# ESP32.net
KiCad netlist of a schematic drawn in Altium Designer
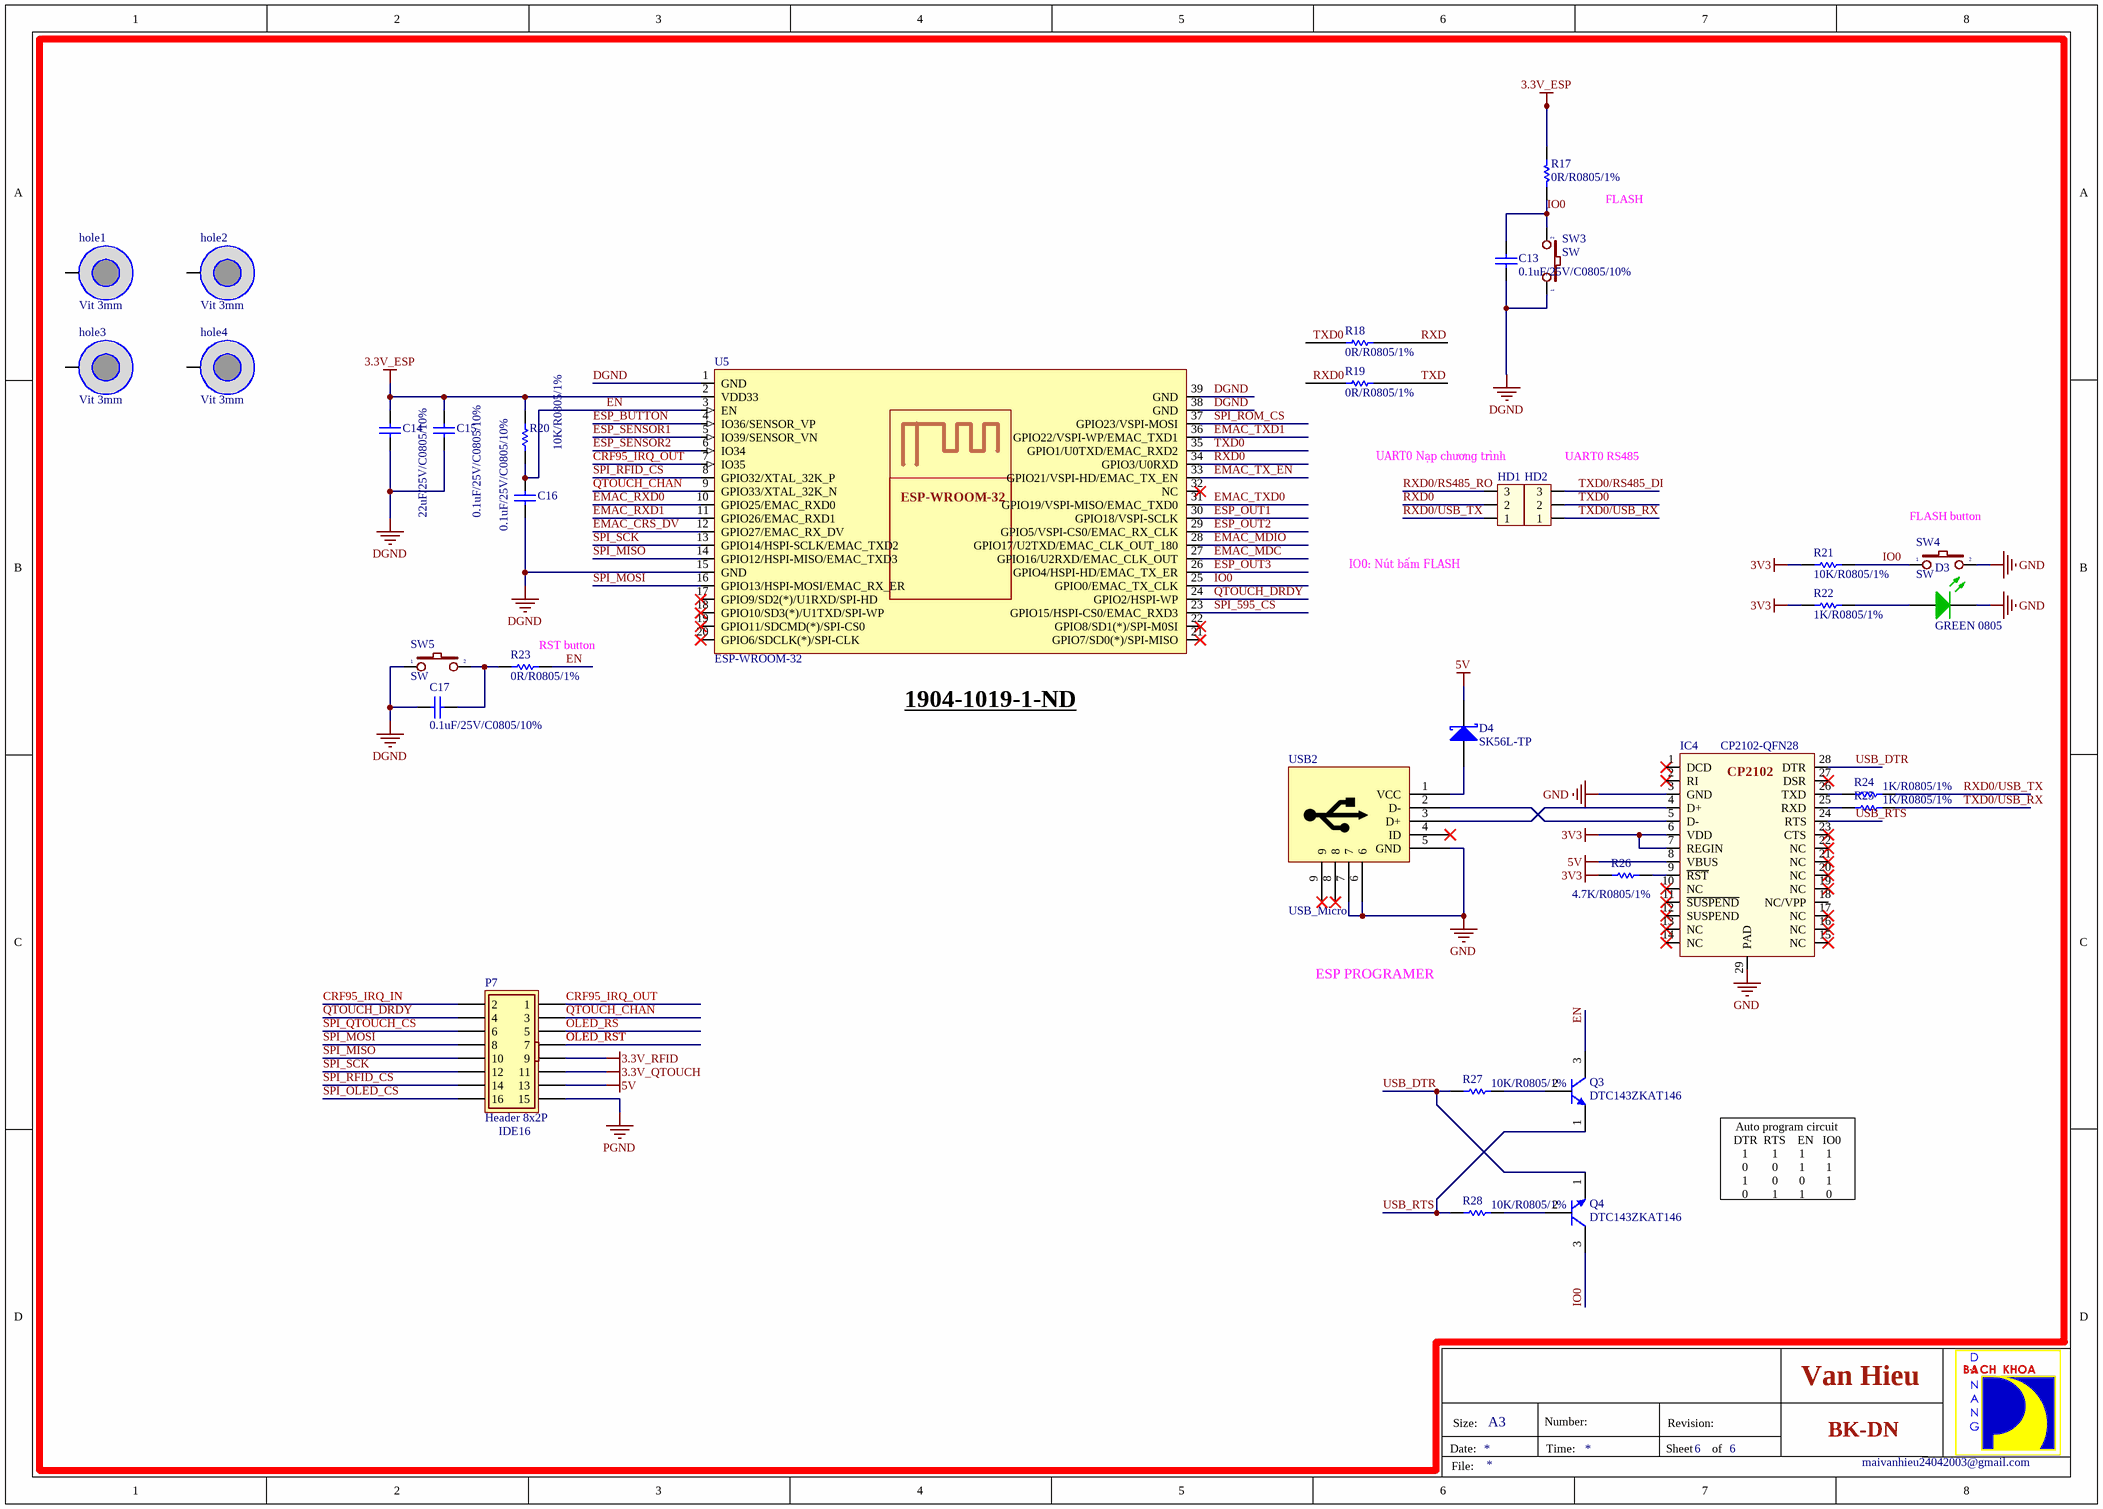
[diagram p0: ESP32.SchDoc]

(export (version "E")
  (design (tool "Eeschema 10.0.6"))
  (components
    (comp (ref "C13")
      (value "0.1uF/25V/C0805/10%")
      (footprint "CAP_CERA_C2012(CC0805INCH)")
      (description "0.1µF ±10% 25V Ceramic Capacitor X7R 0805 (2012 Metric)")
      (libsource (lib "GSHT_181013") (part "0.1uF/50V/C0603/10%"))
    )
    (comp (ref "C14")
      (value "22uF/25V/C0805/10%")
      (footprint "CAP_CERA_C2012(CC0805INCH)")
      (description "22µF ±20% 25V Ceramic Capacitor X5R 0805 (2012 Metric)")
      (fields (field (name "MANUFACTURER") "Tariff Applied"))
      (libsource (lib "GSHT_181013") (part "0.1uF/50V/C0603/10%"))
    )
    (comp (ref "C15")
      (value "0.1uF/25V/C0805/10%")
      (footprint "CAP_CERA_C2012(CC0805INCH)")
      (description "0.1µF ±10% 25V Ceramic Capacitor X7R 0805 (2012 Metric)")
      (libsource (lib "GSHT_181013") (part "0.1uF/50V/C0603/10%"))
    )
    (comp (ref "C16")
      (value "0.1uF/25V/C0805/10%")
      (footprint "CAP_CERA_C2012(CC0805INCH)")
      (description "0.1µF ±10% 25V Ceramic Capacitor X7R 0805 (2012 Metric)")
      (libsource (lib "GSHT_181013") (part "0.1uF/50V/C0603/10%"))
    )
    (comp (ref "C17")
      (value "0.1uF/25V/C0805/10%")
      (footprint "CAP_CERA_C2012(CC0805INCH)")
      (description "0.1µF ±10% 25V Ceramic Capacitor X7R 0805 (2012 Metric)")
      (libsource (lib "GSHT_181013") (part "0.1uF/50V/C0603/10%"))
    )
    (comp (ref "D3")
      (value "GREEN 0805")
      (footprint "Led 0805G")
      (description "Green 571nm LED Indication - Discrete 2V 0805 (2012 Metric)")
      (libsource (lib "GSHT_181013") (part "LED GREEN 0603"))
    )
    (comp (ref "D4")
      (value "SK56L-TP")
      (footprint "30# SK56L-TPMSCT-ND")
      (description "DIODE SCHOTTKY 60V 5A DO214AB")
      (libsource (lib "GSHT_181013") (part "30# SK56L-TP"))
    )
    (comp (ref "HD1") (value "Header 3") (footprint "Header_3") (libsource (lib "") (part "Header3_1")))
    (comp (ref "HD2") (value "Header 3") (footprint "Header_3") (libsource (lib "lpson") (part "Header3")))
    (comp (ref "hole1") (value "Vit 3mm") (footprint "Screw 3.0") (libsource (lib "lpson") (part "Vit 3mm")))
    (comp (ref "hole2") (value "Vit 3mm") (footprint "Screw 3.0") (libsource (lib "lpson") (part "Vit 3mm")))
    (comp (ref "hole3") (value "Vit 3mm") (footprint "Screw 3.0") (libsource (lib "lpson") (part "Vit 3mm")))
    (comp (ref "hole4") (value "Vit 3mm") (footprint "Screw 3.0") (libsource (lib "lpson") (part "Vit 3mm")))
    (comp (ref "IC4") (value "CP2102-QFN28") (footprint "CP2102") (libsource (lib "lpson") (part "CP2102")))
    (comp (ref "P7")
      (value "Header 8x2P")
      (footprint "LPSON_CON:Header IDE16 8x2 -")
      (description "IDE16 Đực Thẳng 2.54MM")
      (libsource (lib "lpson") (part "Header IDE 8x2P"))
    )
    (comp (ref "Q3")
      (value "DTC143ZKAT146")
      (footprint "6# DTC143ZKAT146-E")
      (description "Pre-Biased Bipolar Transistor (BJT) NPN - Pre-Biased 50V 100mA 250MHz 200mW Surface Mount SMT3")
      (libsource (lib "GSHT_181013") (part "6#DTC143ZKAT146"))
    )
    (comp (ref "Q4")
      (value "DTC143ZKAT146")
      (footprint "6# DTC143ZKAT146-E")
      (description "Pre-Biased Bipolar Transistor (BJT) NPN - Pre-Biased 50V 100mA 250MHz 200mW Surface Mount SMT3")
      (libsource (lib "GSHT_181013") (part "6#DTC143ZKAT146"))
    )
    (comp (ref "R17")
      (value "0R/R0805/1%")
      (footprint "Res 0805 SMD")
      (description "0 Ohms Jumper 0.125W, 1/8W Chip Resistor 0805 (2012 Metric) Automotive AEC-Q200 Thick Film")
      (libsource (lib "GSHT_181013") (part "200K/R0603/1%"))
    )
    (comp (ref "R18")
      (value "0R/R0805/1%")
      (footprint "Res 0805 SMD")
      (description "0 Ohms Jumper 0.125W, 1/8W Chip Resistor 0805 (2012 Metric) Automotive AEC-Q200 Thick Film")
      (libsource (lib "GSHT_181013") (part "10K/R0603/1%"))
    )
    (comp (ref "R19")
      (value "0R/R0805/1%")
      (footprint "Res 0805 SMD")
      (description "0 Ohms Jumper 0.125W, 1/8W Chip Resistor 0805 (2012 Metric) Automotive AEC-Q200 Thick Film")
      (libsource (lib "GSHT_181013") (part "10K/R0603/1%"))
    )
    (comp (ref "R20")
      (value "10K/R0805/1%")
      (footprint "Res 0805 SMD")
      (description "10 kOhms ±1% 0.125W, 1/8W Chip Resistor 0805 (2012 Metric) Thick Film")
      (libsource (lib "GSHT_181013") (part "200K/R0603/1%"))
    )
    (comp (ref "R21")
      (value "10K/R0805/1%")
      (footprint "Res 0805 SMD")
      (description "10 kOhms ±1% 0.125W, 1/8W Chip Resistor 0805 (2012 Metric) Thick Film")
      (libsource (lib "GSHT_181013") (part "200K/R0603/1%"))
    )
    (comp (ref "R22")
      (value "1K/R0805/1%")
      (footprint "Res 0805 SMD")
      (description "1 kOhms ±1% 0.125W, 1/8W Chip Resistor 0805 (2012 Metric) Automotive AEC-Q200 Thick Film")
      (libsource (lib "GSHT_181013") (part "200K/R0603/1%"))
    )
    (comp (ref "R23")
      (value "0R/R0805/1%")
      (footprint "Res 0805 SMD")
      (description "0 Ohms Jumper 0.125W, 1/8W Chip Resistor 0805 (2012 Metric) Automotive AEC-Q200 Thick Film")
      (libsource (lib "GSHT_181013") (part "200K/R0603/1%"))
    )
    (comp (ref "R24")
      (value "1K/R0805/1%")
      (footprint "Res 0805 SMD")
      (description "1 kOhms ±1% 0.125W, 1/8W Chip Resistor 0805 (2012 Metric) Automotive AEC-Q200 Thick Film")
      (libsource (lib "GSHT_181013") (part "34.8K/R0805/1%"))
    )
    (comp (ref "R25")
      (value "1K/R0805/1%")
      (footprint "Res 0805 SMD")
      (description "1 kOhms ±1% 0.125W, 1/8W Chip Resistor 0805 (2012 Metric) Automotive AEC-Q200 Thick Film")
      (libsource (lib "GSHT_181013") (part "34.8K/R0805/1%"))
    )
    (comp (ref "R26")
      (value "4.7K/R0805/1%")
      (footprint "Res 0805 SMD")
      (description "4.7 kOhms ±1% 0.125W, 1/8W Chip Resistor 0805 (2012 Metric) Thick Film")
      (libsource (lib "GSHT_181013") (part "34.8K/R0805/1%"))
    )
    (comp (ref "R27")
      (value "10K/R0805/1%")
      (footprint "Res 0805 SMD")
      (description "10 kOhms ±1% 0.125W, 1/8W Chip Resistor 0805 (2012 Metric) Thick Film")
      (libsource (lib "GSHT_181013") (part "34.8K/R0805/1%"))
    )
    (comp (ref "R28")
      (value "10K/R0805/1%")
      (footprint "Res 0805 SMD")
      (description "10 kOhms ±1% 0.125W, 1/8W Chip Resistor 0805 (2012 Metric) Thick Film")
      (libsource (lib "GSHT_181013") (part "34.8K/R0805/1%"))
    )
    (comp (ref "SW3")
      (value "SW")
      (footprint "BUTTON 2PIN TRON")
      (description "Switch button 2 pin")
      (libsource (lib "lpson") (part "SW2"))
    )
    (comp (ref "SW4")
      (value "SW")
      (footprint "BUTTON 2PIN TRON")
      (description "Switch button 2 pin")
      (libsource (lib "lpson") (part "SW2"))
    )
    (comp (ref "SW5")
      (value "SW")
      (footprint "BUTTON 2PIN TRON")
      (description "Switch button 2 pin")
      (libsource (lib "lpson") (part "SW2"))
    )
    (comp (ref "U5")
      (value "ESP-WROOM-32")
      (footprint "ESP32 WROOM")
      (libsource (lib "lpson") (part "ESP-WROOM-32"))
    )
    (comp (ref "USB2") (value "USB_Micro") (footprint "USBMNIB") (libsource (lib "lpson") (part "USB_MINI")))
  )
  (nets
    (net (code "1") (name "/CRF95_IRQ_IN") (class "Default")
      (node (ref "P7") (pin "2") (pinfunction "2_2") (pintype "passive"))
    )
    (net (code "2") (name "/CRF95_IRQ_OUT") (class "Default")
      (node (ref "P7") (pin "1") (pinfunction "1_1") (pintype "passive"))
      (node (ref "U5") (pin "7") (pinfunction "IO35_7") (pintype "input"))
    )
    (net (code "3") (name "/EMAC_CRS_DV") (class "Default")
      (node (ref "U5") (pin "12") (pinfunction "GPIO27/EMAC_RX_DV_12") (pintype "passive"))
    )
    (net (code "4") (name "/EMAC_MDC") (class "Default")
      (node (ref "U5") (pin "27") (pinfunction "GPIO16/U2RXD/EMAC_CLK_OUT_27") (pintype "passive"))
    )
    (net (code "5") (name "/EMAC_MDIO") (class "Default")
      (node (ref "U5") (pin "28") (pinfunction "GPIO17/U2TXD/EMAC_CLK_OUT_180_28") (pintype "passive"))
    )
    (net (code "6") (name "/EMAC_RXD0") (class "Default")
      (node (ref "U5") (pin "10") (pinfunction "GPIO25/EMAC_RXD0_10") (pintype "passive"))
    )
    (net (code "7") (name "/EMAC_RXD1") (class "Default")
      (node (ref "U5") (pin "11") (pinfunction "GPIO26/EMAC_RXD1_11") (pintype "passive"))
    )
    (net (code "8") (name "/EMAC_TXD0") (class "Default")
      (node (ref "U5") (pin "31") (pinfunction "GPIO19/VSPI-MISO/EMAC_TXD0_31") (pintype "passive"))
    )
    (net (code "9") (name "/EMAC_TXD1") (class "Default")
      (node (ref "U5") (pin "36") (pinfunction "GPIO22/VSPI-WP/EMAC_TXD1_36") (pintype "passive"))
    )
    (net (code "10") (name "/EMAC_TX_EN") (class "Default")
      (node (ref "U5") (pin "33") (pinfunction "GPIO21/VSPI-HD/EMAC_TX_EN_33") (pintype "passive"))
    )
    (net (code "11") (name "/EN") (class "Default")
      (node (ref "C16") (pin "2") (pinfunction "2_2") (pintype "passive"))
      (node (ref "Q3") (pin "3") (pinfunction "C_3") (pintype "passive"))
      (node (ref "R20") (pin "2") (pinfunction "2_2") (pintype "passive"))
      (node (ref "R23") (pin "2") (pinfunction "2_2") (pintype "passive"))
      (node (ref "U5") (pin "3") (pinfunction "EN_3") (pintype "input"))
    )
    (net (code "12") (name "/ESP_BUTTON") (class "Default")
      (node (ref "U5") (pin "4") (pinfunction "IO36/SENSOR_VP_4") (pintype "input"))
    )
    (net (code "13") (name "/ESP_OUT1") (class "Default")
      (node (ref "U5") (pin "30") (pinfunction "GPIO18/VSPI-SCLK_30") (pintype "passive"))
    )
    (net (code "14") (name "/ESP_OUT2") (class "Default")
      (node (ref "U5") (pin "29") (pinfunction "GPIO5/VSPI-CS0/EMAC_RX_CLK_29") (pintype "passive"))
    )
    (net (code "15") (name "/ESP_OUT3") (class "Default")
      (node (ref "U5") (pin "26") (pinfunction "GPIO4/HSPI-HD/EMAC_TX_ER_26") (pintype "passive"))
    )
    (net (code "16") (name "/ESP_SENSOR1") (class "Default")
      (node (ref "U5") (pin "5") (pinfunction "IO39/SENSOR_VN_5") (pintype "input"))
    )
    (net (code "17") (name "/ESP_SENSOR2") (class "Default")
      (node (ref "U5") (pin "6") (pinfunction "IO34_6") (pintype "input"))
    )
    (net (code "18") (name "/IO0") (class "Default")
      (node (ref "C13") (pin "1") (pinfunction "1_1") (pintype "passive"))
      (node (ref "Q4") (pin "3") (pinfunction "C_3") (pintype "passive"))
      (node (ref "R17") (pin "1") (pinfunction "1_1") (pintype "passive"))
      (node (ref "R21") (pin "2") (pinfunction "2_2") (pintype "passive"))
      (node (ref "SW3") (pin "2") (pinfunction "2_2") (pintype "passive"))
      (node (ref "SW4") (pin "1") (pinfunction "1_1") (pintype "passive"))
      (node (ref "U5") (pin "25") (pinfunction "GPIO0/EMAC_TX_CLK_25") (pintype "passive"))
    )
    (net (code "19") (name "/OLED_RS") (class "Default")
      (node (ref "P7") (pin "5") (pinfunction "5_5") (pintype "passive"))
    )
    (net (code "20") (name "/OLED_RST") (class "Default")
      (node (ref "P7") (pin "7") (pinfunction "7_7") (pintype "passive"))
    )
    (net (code "21") (name "/QTOUCH_CHAN") (class "Default")
      (node (ref "P7") (pin "3") (pinfunction "3_3") (pintype "passive"))
      (node (ref "U5") (pin "9") (pinfunction "GPIO33/XTAL_32K_N_9") (pintype "passive"))
    )
    (net (code "22") (name "/QTOUCH_DRDY") (class "Default")
      (node (ref "P7") (pin "4") (pinfunction "4_4") (pintype "passive"))
      (node (ref "U5") (pin "24") (pinfunction "GPIO2/HSPI-WP_24") (pintype "passive"))
    )
    (net (code "23") (name "/RXD") (class "Default")
      (node (ref "R18") (pin "1") (pinfunction "1_1") (pintype "passive"))
    )
    (net (code "24") (name "/RXD0") (class "Default")
      (node (ref "HD1") (pin "2") (pinfunction "2_2") (pintype "passive"))
      (node (ref "R19") (pin "2") (pinfunction "2_2") (pintype "passive"))
      (node (ref "U5") (pin "34") (pinfunction "GPIO3/U0RXD_34") (pintype "passive"))
    )
    (net (code "25") (name "/RXD0{slash}RS485_RO") (class "Default")
      (node (ref "HD1") (pin "3") (pinfunction "3_3") (pintype "passive"))
    )
    (net (code "26") (name "/RXD0{slash}USB_TX") (class "Default")
      (node (ref "HD1") (pin "1") (pinfunction "1_1") (pintype "passive"))
      (node (ref "R24") (pin "1") (pinfunction "1_1") (pintype "passive"))
    )
    (net (code "27") (name "/SPI_595_CS") (class "Default")
      (node (ref "U5") (pin "23") (pinfunction "GPIO15/HSPI-CS0/EMAC_RXD3_23") (pintype "passive"))
    )
    (net (code "28") (name "/SPI_MISO") (class "Default")
      (node (ref "P7") (pin "10") (pinfunction "10_10") (pintype "passive"))
      (node (ref "U5") (pin "14") (pinfunction "GPIO12/HSPI-MISO/EMAC_TXD3_14") (pintype "passive"))
    )
    (net (code "29") (name "/SPI_MOSI") (class "Default")
      (node (ref "P7") (pin "8") (pinfunction "8_8") (pintype "passive"))
      (node (ref "U5") (pin "16") (pinfunction "GPIO13/HSPI-MOSI/EMAC_RX_ER_16") (pintype "passive"))
    )
    (net (code "30") (name "/SPI_OLED_CS") (class "Default")
      (node (ref "P7") (pin "16") (pinfunction "16_16") (pintype "passive"))
    )
    (net (code "31") (name "/SPI_QTOUCH_CS") (class "Default")
      (node (ref "P7") (pin "6") (pinfunction "6_6") (pintype "passive"))
    )
    (net (code "32") (name "/SPI_RFID_CS") (class "Default")
      (node (ref "P7") (pin "14") (pinfunction "14_14") (pintype "passive"))
      (node (ref "U5") (pin "8") (pinfunction "GPIO32/XTAL_32K_P_8") (pintype "passive"))
    )
    (net (code "33") (name "/SPI_ROM_CS") (class "Default")
      (node (ref "U5") (pin "37") (pinfunction "GPIO23/VSPI-MOSI_37") (pintype "passive"))
    )
    (net (code "34") (name "/SPI_SCK") (class "Default")
      (node (ref "P7") (pin "12") (pinfunction "12_12") (pintype "passive"))
      (node (ref "U5") (pin "13") (pinfunction "GPIO14/HSPI-SCLK/EMAC_TXD2_13") (pintype "passive"))
    )
    (net (code "35") (name "/TXD") (class "Default")
      (node (ref "R19") (pin "1") (pinfunction "1_1") (pintype "passive"))
    )
    (net (code "36") (name "/TXD0") (class "Default")
      (node (ref "HD2") (pin "2") (pinfunction "2_2") (pintype "passive"))
      (node (ref "R18") (pin "2") (pinfunction "2_2") (pintype "passive"))
      (node (ref "U5") (pin "35") (pinfunction "GPIO1/U0TXD/EMAC_RXD2_35") (pintype "passive"))
    )
    (net (code "37") (name "/TXD0{slash}RS485_DI") (class "Default")
      (node (ref "HD2") (pin "3") (pinfunction "3_3") (pintype "passive"))
    )
    (net (code "38") (name "/TXD0{slash}USB_RX") (class "Default")
      (node (ref "HD2") (pin "1") (pinfunction "1_1") (pintype "passive"))
      (node (ref "R25") (pin "1") (pinfunction "1_1") (pintype "passive"))
    )
    (net (code "39") (name "/USB_DTR") (class "Default")
      (node (ref "IC4") (pin "28") (pinfunction "DTR_28") (pintype "passive"))
      (node (ref "Q4") (pin "1") (pinfunction "E_1") (pintype "passive"))
      (node (ref "R27") (pin "2") (pinfunction "2_2") (pintype "passive"))
    )
    (net (code "40") (name "/USB_RTS") (class "Default")
      (node (ref "IC4") (pin "24") (pinfunction "RTS_24") (pintype "passive"))
      (node (ref "Q3") (pin "1") (pinfunction "E_1") (pintype "passive"))
      (node (ref "R28") (pin "2") (pinfunction "2_2") (pintype "passive"))
    )
    (net (code "41") (name "3.3V_ESP") (class "Default")
      (node (ref "C14") (pin "2") (pinfunction "2_2") (pintype "passive"))
      (node (ref "C15") (pin "2") (pinfunction "2_2") (pintype "passive"))
      (node (ref "R17") (pin "2") (pinfunction "2_2") (pintype "passive"))
      (node (ref "R20") (pin "1") (pinfunction "1_1") (pintype "passive"))
      (node (ref "U5") (pin "2") (pinfunction "VDD33_2") (pintype "passive"))
    )
    (net (code "42") (name "3.3V_QTOUCH") (class "Default")
      (node (ref "P7") (pin "11") (pinfunction "11_11") (pintype "passive"))
    )
    (net (code "43") (name "3.3V_RFID") (class "Default")
      (node (ref "P7") (pin "9") (pinfunction "9_9") (pintype "passive"))
    )
    (net (code "44") (name "3V3") (class "Default")
      (node (ref "IC4") (pin "6") (pinfunction "VDD_6") (pintype "passive"))
      (node (ref "IC4") (pin "7") (pinfunction "REGIN_7") (pintype "passive"))
      (node (ref "R21") (pin "1") (pinfunction "1_1") (pintype "passive"))
      (node (ref "R22") (pin "1") (pinfunction "1_1") (pintype "passive"))
      (node (ref "R26") (pin "1") (pinfunction "1_1") (pintype "passive"))
    )
    (net (code "45") (name "5V") (class "Default")
      (node (ref "D4") (pin "2") (pinfunction "K_2") (pintype "passive"))
      (node (ref "IC4") (pin "8") (pinfunction "VBUS_8") (pintype "passive"))
      (node (ref "P7") (pin "13") (pinfunction "13_13") (pintype "passive"))
    )
    (net (code "46") (name "DGND") (class "Default")
      (node (ref "C13") (pin "2") (pinfunction "2_2") (pintype "passive"))
      (node (ref "C14") (pin "1") (pinfunction "1_1") (pintype "passive"))
      (node (ref "C15") (pin "1") (pinfunction "1_1") (pintype "passive"))
      (node (ref "C16") (pin "1") (pinfunction "1_1") (pintype "passive"))
      (node (ref "C17") (pin "2") (pinfunction "2_2") (pintype "passive"))
      (node (ref "SW3") (pin "1") (pinfunction "1_1") (pintype "passive"))
      (node (ref "SW5") (pin "1") (pinfunction "1_1") (pintype "passive"))
      (node (ref "U5") (pin "1") (pinfunction "GND_1") (pintype "passive"))
      (node (ref "U5") (pin "15") (pinfunction "GND_15") (pintype "passive"))
      (node (ref "U5") (pin "38") (pinfunction "GND_38") (pintype "passive"))
      (node (ref "U5") (pin "39") (pinfunction "GND_39") (pintype "passive"))
    )
    (net (code "47") (name "GND") (class "Default")
      (node (ref "D3") (pin "2") (pinfunction "K_2") (pintype "passive"))
      (node (ref "IC4") (pin "29") (pinfunction "PAD_29") (pintype "passive"))
      (node (ref "IC4") (pin "3") (pinfunction "GND_3") (pintype "passive"))
      (node (ref "SW4") (pin "2") (pinfunction "2_2") (pintype "passive"))
      (node (ref "USB2") (pin "5") (pinfunction "GND_5") (pintype "passive"))
      (node (ref "USB2") (pin "6") (pinfunction "6_6") (pintype "passive"))
      (node (ref "USB2") (pin "7") (pinfunction "7_7") (pintype "passive"))
    )
    (net (code "48") (name "Net-(C17-Pad1)") (class "Default")
      (node (ref "C17") (pin "1") (pinfunction "1_1") (pintype "passive"))
      (node (ref "R23") (pin "1") (pinfunction "1_1") (pintype "passive"))
      (node (ref "SW5") (pin "2") (pinfunction "2_2") (pintype "passive"))
    )
    (net (code "49") (name "Net-(D3-A)") (class "Default")
      (node (ref "D3") (pin "1") (pinfunction "A_1") (pintype "passive"))
      (node (ref "R22") (pin "2") (pinfunction "2_2") (pintype "passive"))
    )
    (net (code "50") (name "Net-(D4-A)") (class "Default")
      (node (ref "D4") (pin "1") (pinfunction "A_1") (pintype "passive"))
      (node (ref "USB2") (pin "1") (pinfunction "VCC_1") (pintype "passive"))
    )
    (net (code "51") (name "Net-(IC4-D+)") (class "Default")
      (node (ref "IC4") (pin "4") (pinfunction "D+_4") (pintype "passive"))
      (node (ref "USB2") (pin "3") (pinfunction "D+_3") (pintype "passive"))
    )
    (net (code "52") (name "Net-(IC4-D-)") (class "Default")
      (node (ref "IC4") (pin "5") (pinfunction "D-_5") (pintype "passive"))
      (node (ref "USB2") (pin "2") (pinfunction "D-_2") (pintype "passive"))
    )
    (net (code "53") (name "Net-(IC4-RXD)") (class "Default")
      (node (ref "IC4") (pin "25") (pinfunction "RXD_25") (pintype "passive"))
      (node (ref "R25") (pin "2") (pinfunction "2_2") (pintype "passive"))
    )
    (net (code "54") (name "Net-(IC4-TXD)") (class "Default")
      (node (ref "IC4") (pin "26") (pinfunction "TXD_26") (pintype "passive"))
      (node (ref "R24") (pin "2") (pinfunction "2_2") (pintype "passive"))
    )
    (net (code "55") (name "Net-(IC4-~{RST})") (class "Default")
      (node (ref "IC4") (pin "9") (pinfunction "~{RST}_9") (pintype "passive"))
      (node (ref "R26") (pin "2") (pinfunction "2_2") (pintype "passive"))
    )
    (net (code "56") (name "Net-(Q3-B)") (class "Default")
      (node (ref "Q3") (pin "2") (pinfunction "B_2") (pintype "passive"))
      (node (ref "R27") (pin "1") (pinfunction "1_1") (pintype "passive"))
    )
    (net (code "57") (name "Net-(Q4-B)") (class "Default")
      (node (ref "Q4") (pin "2") (pinfunction "B_2") (pintype "passive"))
      (node (ref "R28") (pin "1") (pinfunction "1_1") (pintype "passive"))
    )
    (net (code "58") (name "PGND") (class "Default")
      (node (ref "P7") (pin "15") (pinfunction "15_15") (pintype "passive"))
    )
    (net (code "59") (name "unconnected-(IC4-CTS-Pad23)") (class "Default")
      (node (ref "IC4") (pin "23") (pinfunction "CTS_23") (pintype "passive+no_connect"))
    )
    (net (code "60") (name "unconnected-(IC4-DCD-Pad1)") (class "Default")
      (node (ref "IC4") (pin "1") (pinfunction "DCD_1") (pintype "passive+no_connect"))
    )
    (net (code "61") (name "unconnected-(IC4-DSR-Pad27)") (class "Default")
      (node (ref "IC4") (pin "27") (pinfunction "DSR_27") (pintype "passive+no_connect"))
    )
    (net (code "62") (name "unconnected-(IC4-NC-Pad10)") (class "Default")
      (node (ref "IC4") (pin "10") (pinfunction "NC_10") (pintype "passive+no_connect"))
    )
    (net (code "63") (name "unconnected-(IC4-NC-Pad13)") (class "Default")
      (node (ref "IC4") (pin "13") (pinfunction "NC_13") (pintype "passive+no_connect"))
    )
    (net (code "64") (name "unconnected-(IC4-NC-Pad14)") (class "Default")
      (node (ref "IC4") (pin "14") (pinfunction "NC_14") (pintype "passive+no_connect"))
    )
    (net (code "65") (name "unconnected-(IC4-NC-Pad15)") (class "Default")
      (node (ref "IC4") (pin "15") (pinfunction "NC_15") (pintype "passive+no_connect"))
    )
    (net (code "66") (name "unconnected-(IC4-NC-Pad16)") (class "Default")
      (node (ref "IC4") (pin "16") (pinfunction "NC_16") (pintype "passive+no_connect"))
    )
    (net (code "67") (name "unconnected-(IC4-NC-Pad17)") (class "Default")
      (node (ref "IC4") (pin "17") (pinfunction "NC_17") (pintype "passive+no_connect"))
    )
    (net (code "68") (name "unconnected-(IC4-NC-Pad19)") (class "Default")
      (node (ref "IC4") (pin "19") (pinfunction "NC_19") (pintype "passive+no_connect"))
    )
    (net (code "69") (name "unconnected-(IC4-NC-Pad20)") (class "Default")
      (node (ref "IC4") (pin "20") (pinfunction "NC_20") (pintype "passive+no_connect"))
    )
    (net (code "70") (name "unconnected-(IC4-NC-Pad21)") (class "Default")
      (node (ref "IC4") (pin "21") (pinfunction "NC_21") (pintype "passive+no_connect"))
    )
    (net (code "71") (name "unconnected-(IC4-NC-Pad22)") (class "Default")
      (node (ref "IC4") (pin "22") (pinfunction "NC_22") (pintype "passive+no_connect"))
    )
    (net (code "72") (name "unconnected-(IC4-NC{slash}VPP-Pad18)") (class "Default")
      (node (ref "IC4") (pin "18") (pinfunction "NC/VPP_18") (pintype "passive"))
    )
    (net (code "73") (name "unconnected-(IC4-RI-Pad2)") (class "Default")
      (node (ref "IC4") (pin "2") (pinfunction "RI_2") (pintype "passive+no_connect"))
    )
    (net (code "74") (name "unconnected-(IC4-SUSPEND-Pad12)") (class "Default")
      (node (ref "IC4") (pin "12") (pinfunction "SUSPEND_12") (pintype "passive+no_connect"))
    )
    (net (code "75") (name "unconnected-(IC4-~{SUSPEND}-Pad11)") (class "Default")
      (node (ref "IC4") (pin "11") (pinfunction "~{SUSPEND}_11") (pintype "passive+no_connect"))
    )
    (net (code "76") (name "unconnected-(U5-GPIO6{slash}SDCLK(*){slash}SPI-CLK-Pad20)") (class "Default")
      (node (ref "U5") (pin "20") (pinfunction "GPIO6/SDCLK(*)/SPI-CLK_20") (pintype "passive+no_connect"))
    )
    (net (code "77") (name "unconnected-(U5-GPIO7{slash}SD0(*){slash}SPI-MISO-Pad21)") (class "Default")
      (node (ref "U5") (pin "21") (pinfunction "GPIO7/SD0(*)/SPI-MISO_21") (pintype "passive+no_connect"))
    )
    (net (code "78") (name "unconnected-(U5-GPIO8{slash}SD1(*){slash}SPI-M0SI-Pad22)") (class "Default")
      (node (ref "U5") (pin "22") (pinfunction "GPIO8/SD1(*)/SPI-M0SI_22") (pintype "passive+no_connect"))
    )
    (net (code "79") (name "unconnected-(U5-GPIO9{slash}SD2(*){slash}U1RXD{slash}SPI-HD-Pad17)") (class "Default")
      (node (ref "U5") (pin "17") (pinfunction "GPIO9/SD2(*)/U1RXD/SPI-HD_17") (pintype "passive+no_connect"))
    )
    (net (code "80") (name "unconnected-(U5-GPIO10{slash}SD3(*){slash}U1TXD{slash}SPI-WP-Pad18)") (class "Default")
      (node (ref "U5") (pin "18") (pinfunction "GPIO10/SD3(*)/U1TXD/SPI-WP_18") (pintype "passive+no_connect"))
    )
    (net (code "81") (name "unconnected-(U5-GPIO11{slash}SDCMD(*){slash}SPI-CS0-Pad19)") (class "Default")
      (node (ref "U5") (pin "19") (pinfunction "GPIO11/SDCMD(*)/SPI-CS0_19") (pintype "passive+no_connect"))
    )
    (net (code "82") (name "unconnected-(U5-NC-Pad32)") (class "Default")
      (node (ref "U5") (pin "32") (pinfunction "NC_32") (pintype "passive+no_connect"))
    )
    (net (code "83") (name "unconnected-(USB2-ID-Pad4)") (class "Default")
      (node (ref "USB2") (pin "4") (pinfunction "ID_4") (pintype "passive+no_connect"))
    )
    (net (code "84") (name "unconnected-(USB2-Pad8)") (class "Default")
      (node (ref "USB2") (pin "8") (pinfunction "8_8") (pintype "passive+no_connect"))
    )
    (net (code "85") (name "unconnected-(USB2-Pad9)") (class "Default")
      (node (ref "USB2") (pin "9") (pinfunction "9_9") (pintype "passive+no_connect"))
    )
    (net (code "86") (name "unconnected-(hole1-hole-Pad1)") (class "Default")
      (node (ref "hole1") (pin "1") (pinfunction "hole_1") (pintype "passive"))
    )
    (net (code "87") (name "unconnected-(hole2-hole-Pad1)") (class "Default")
      (node (ref "hole2") (pin "1") (pinfunction "hole_1") (pintype "passive"))
    )
    (net (code "88") (name "unconnected-(hole3-hole-Pad1)") (class "Default")
      (node (ref "hole3") (pin "1") (pinfunction "hole_1") (pintype "passive"))
    )
    (net (code "89") (name "unconnected-(hole4-hole-Pad1)") (class "Default")
      (node (ref "hole4") (pin "1") (pinfunction "hole_1") (pintype "passive"))
    )
  )
)
